# design.net
KiCad netlist of a schematic drawn in EasyEDA Pro
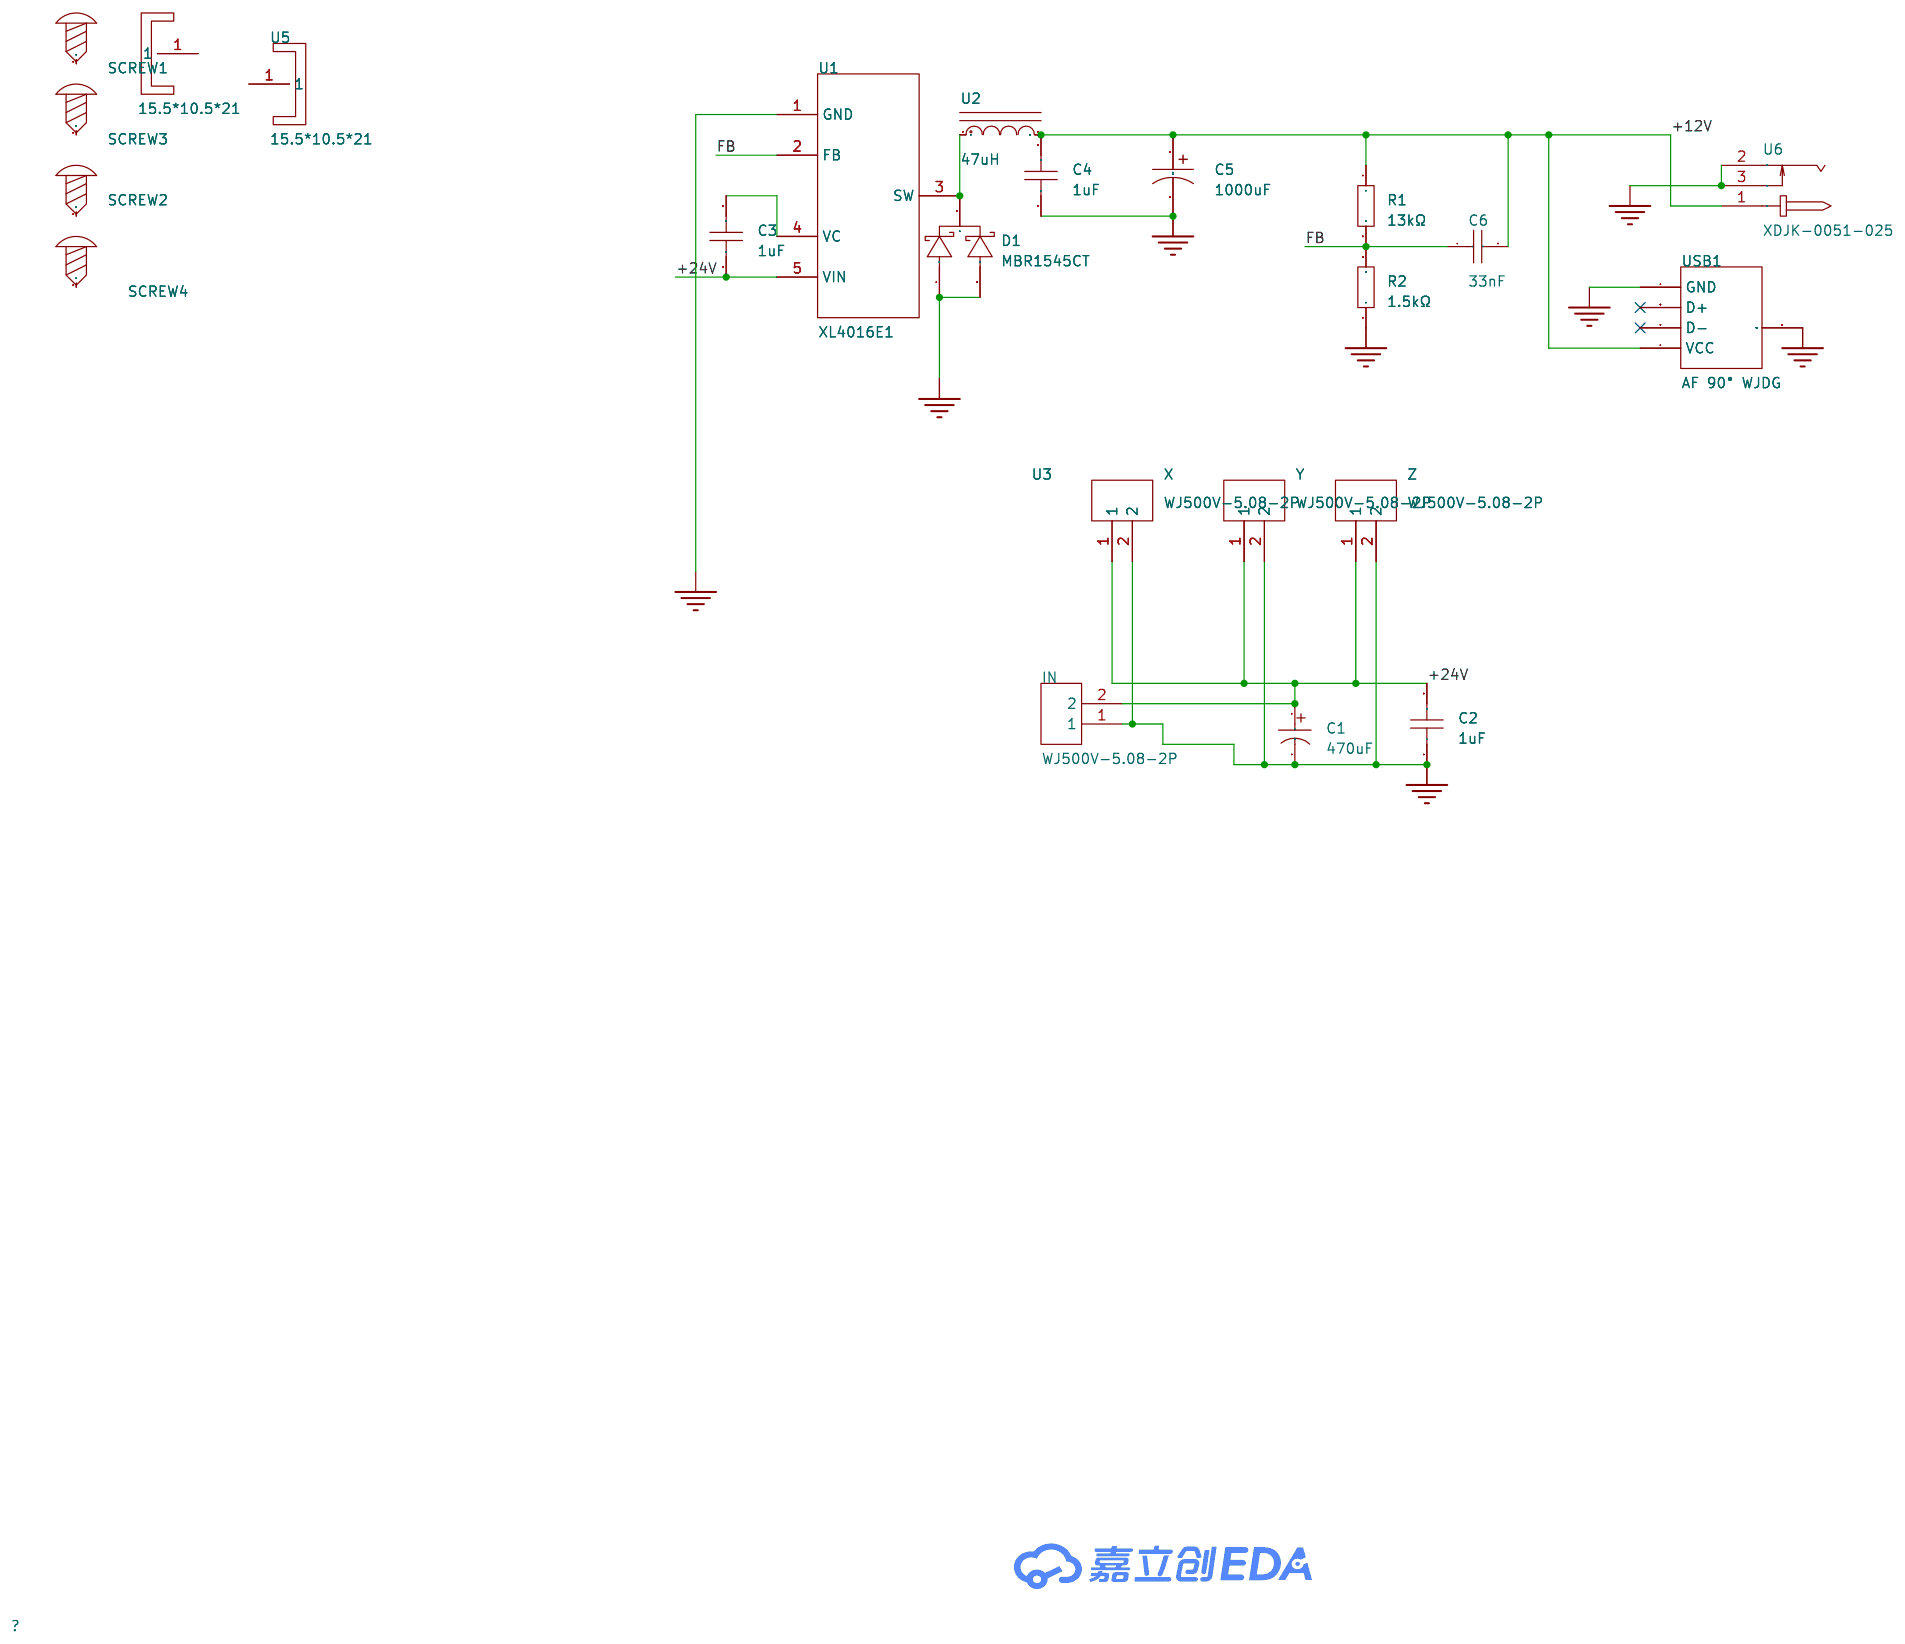
[diagram p0: schematic sheet]

(export (version "E")
  (design (tool "Eeschema 10.0.6"))
  (components
    (comp (ref "C1")
      (value "470uF")
      (footprint "easyedapro:CAP-TH_BD10.0-P5.00-D1.0-FD")
      (description "容值:470uF;精度:±20%;额定电压:50V;")
      (fields (field (name "Manufacturer Part") "ERS1HM471G20OT") (field (name "Manufacturer") "AISHI(艾华集团)"))
      (libsource (lib "easyedapro") (part "ERS1HM471G20OT"))
    )
    (comp (ref "C2")
      (value "1uF")
      (footprint "easyedapro:C0603")
      (description "容值:1uF;精度:±10%;额定电压:50V;材质(温度系数):X5R;")
      (fields
        (field (name "Manufacturer Part") "CL10A105KB8NNNC")
        (field (name "Manufacturer") "SAMSUNG(三星)")
      )
      (libsource (lib "easyedapro") (part "CL10A105KB8NNNC"))
    )
    (comp (ref "C3")
      (value "1uF")
      (footprint "easyedapro:C0603")
      (description "容值:1uF;精度:±10%;额定电压:50V;材质(温度系数):X5R;")
      (fields
        (field (name "Manufacturer Part") "CL10A105KB8NNNC")
        (field (name "Manufacturer") "SAMSUNG(三星)")
      )
      (libsource (lib "easyedapro") (part "CL10A105KB8NNNC"))
    )
    (comp (ref "C4")
      (value "1uF")
      (footprint "easyedapro:C0603")
      (description "容值:1uF;精度:±10%;额定电压:50V;材质(温度系数):X5R;")
      (fields
        (field (name "Manufacturer Part") "CL10A105KB8NNNC")
        (field (name "Manufacturer") "SAMSUNG(三星)")
      )
      (libsource (lib "easyedapro") (part "CL10A105KB8NNNC"))
    )
    (comp (ref "C5")
      (value "1000uF")
      (footprint "easyedapro:CAP-TH_BD10.0-P5.00-D1.0-FD")
      (description "容值:1000uF;精度:±20%;额定电压:25V;纹波电流:450mA@120Hz;等效串联电阻:-;")
      (fields
        (field (name "Manufacturer Part") "01EC4294SHC1000UF25V")
        (field (name "Manufacturer") "KNSCHA(科尼盛)")
      )
      (libsource (lib "easyedapro") (part "01EC4294SHC1000UF25V"))
    )
    (comp (ref "C6")
      (value "33nF")
      (footprint "easyedapro:C0603")
      (description "容值:33nF;精度:±10%;额定电压:50V;材质(温度系数):X7R;")
      (fields
        (field (name "Manufacturer Part") "CL10B333KB8NNNC")
        (field (name "Manufacturer") "SAMSUNG(三星)")
      )
      (libsource (lib "easyedapro") (part "CL10B333KB8NNNC"))
    )
    (comp (ref "D1")
      (value "MBR1545CT")
      (footprint "easyedapro:ITO-220AB-3_L10.0-W4.5-P2.54-R")
      (description "正向压降(Vf):650mV@7.5A;直流反向耐压(Vr):45V;整流电流:15A;")
      (fields (field (name "Manufacturer") "YANGJIE(扬杰)"))
      (libsource (lib "easyedapro") (part "MBR1545CT_C698791"))
    )
    (comp (ref "IN")
      (value "WJ500V-5.08-2P")
      (footprint "easyedapro:CONN-TH_2P-P5.00_WJ500V-5.08-2P")
      (fields (field (name "Manufacturer") "KANGNEX(康奈克斯电气)"))
      (libsource (lib "easyedapro") (part "WJ500V-5.08-2P-14-00A"))
    )
    (comp (ref "R1")
      (value "13kΩ")
      (footprint "easyedapro:R0603")
      (description "电阻类型:厚膜电阻;阻值:13kΩ;精度:±1%;功率:100mW;最大工作电压:75V;温度系数:±100ppm/°C;")
      (fields
        (field (name "Manufacturer Part") "0603WAF1302T5E")
        (field (name "Manufacturer") "UNI-ROYAL(厚声)")
      )
      (libsource (lib "easyedapro") (part "0603WAF1302T5E"))
    )
    (comp (ref "R2")
      (value "1.5kΩ")
      (footprint "easyedapro:R0603")
      (description "电阻类型:厚膜电阻;阻值:1.5kΩ;精度:±1%;功率:100mW;最大工作电压:75V;温度系数:±100ppm/°C;")
      (fields
        (field (name "Manufacturer Part") "0603WAF1501T5E")
        (field (name "Manufacturer") "UNI-ROYAL(厚声)")
      )
      (libsource (lib "easyedapro") (part "0603WAF1501T5E"))
    )
    (comp (ref "SCREW1")
      (value "~")
      (footprint "easyedapro:M3螺丝")
      (libsource (lib "easyedapro") (part "螺丝孔"))
    )
    (comp (ref "SCREW2")
      (value "~")
      (footprint "easyedapro:M3螺丝")
      (libsource (lib "easyedapro") (part "螺丝孔"))
    )
    (comp (ref "SCREW3")
      (value "~")
      (footprint "easyedapro:M3螺丝")
      (libsource (lib "easyedapro") (part "螺丝孔"))
    )
    (comp (ref "SCREW4")
      (value "~")
      (footprint "easyedapro:M3螺丝")
      (libsource (lib "easyedapro") (part "螺丝孔"))
    )
    (comp (ref "U1")
      (value "XL4016E1")
      (footprint "easyedapro:TO-220-5L_L10.2-W4.5-P1.71-L")
      (description "功能类型:降压型;输出类型:可调;工作电压:8V~36V;输出电压:1.25V~32V;输出电流:12A;")
      (fields (field (name "Manufacturer") "XLSEMI(芯龙)"))
      (libsource (lib "easyedapro") (part "XL4016E1"))
    )
    (comp (ref "U2")
      (value "47uH")
      (footprint "easyedapro:IND-TH_L23.2-W9.8_XR080125T101MV1L")
      (description "电感值:47uH;精度:±10%;额定电流:7.8A;类型:磁环电感;")
      (fields (field (name "Manufacturer Part") "XR080125T470MV1L") (field (name "Manufacturer") "XR(祥如)"))
      (libsource (lib "easyedapro") (part "XR080125T470MV1L"))
    )
    (comp (ref "U3")
      (value "15.5*10.5*21")
      (footprint "easyedapro:SINK-TH_L15.0-W10.5-H21.0")
      (description "产品尺寸:15.5*10.5*21MM;材 质:6063-T5;")
      (fields (field (name "Manufacturer") "XSD(鑫顺达)"))
      (libsource (lib "easyedapro") (part "15*10.5*21"))
    )
    (comp (ref "U5")
      (value "15.5*10.5*21")
      (footprint "easyedapro:SINK-TH_L15.0-W10.5-H21.0")
      (description "产品尺寸:15.5*10.5*21MM;材 质:6063-T5;")
      (fields (field (name "Manufacturer") "XSD(鑫顺达)"))
      (libsource (lib "easyedapro") (part "15*10.5*21"))
    )
    (comp (ref "U6")
      (value "XDJK-0051-025")
      (footprint "easyedapro:DC-IN-TH_XDJK-0051-025")
      (fields (field (name "Manufacturer") "LX(连欣科技)"))
      (libsource (lib "easyedapro") (part "XDJK-0051-025"))
    )
    (comp (ref "USB1")
      (value "AF 90° WJDG")
      (footprint "easyedapro:USB-A-TH_AF-WJDG")
      (description "连接器类型:Type-A;标准:USB 2.0;公母:母;安装方式:弯插;触点数量:4P;端口数量:1;额定电流 - 电源:1.5A;工作温度范围:-25°C~+85°C;")
      (fields (field (name "Manufacturer") "SHOU HAN(首韩)"))
      (libsource (lib "easyedapro") (part "AF 90° WJDG"))
    )
    (comp (ref "X")
      (value "WJ500V-5.08-2P")
      (footprint "easyedapro:CONN-TH_2P-P5.00_WJ500V-5.08-2P")
      (fields (field (name "Manufacturer") "KANGNEX(康奈克斯电气)"))
      (libsource (lib "easyedapro") (part "WJ500V-5.08-2P-14-00A"))
    )
    (comp (ref "Y")
      (value "WJ500V-5.08-2P")
      (footprint "easyedapro:CONN-TH_2P-P5.00_WJ500V-5.08-2P")
      (fields (field (name "Manufacturer") "KANGNEX(康奈克斯电气)"))
      (libsource (lib "easyedapro") (part "WJ500V-5.08-2P-14-00A"))
    )
    (comp (ref "Z")
      (value "WJ500V-5.08-2P")
      (footprint "easyedapro:CONN-TH_2P-P5.00_WJ500V-5.08-2P")
      (fields (field (name "Manufacturer") "KANGNEX(康奈克斯电气)"))
      (libsource (lib "easyedapro") (part "WJ500V-5.08-2P-14-00A"))
    )
  )
  (nets
    (net (code "1") (name "/+12V") (class "Default")
      (node (ref "C4") (pin "2") (pinfunction "2_2") (pintype "unspecified"))
      (node (ref "C5") (pin "1") (pinfunction "1_1") (pintype "unspecified"))
      (node (ref "C6") (pin "2") (pinfunction "2_2") (pintype "input"))
      (node (ref "R1") (pin "1") (pinfunction "1_1") (pintype "input"))
      (node (ref "U2") (pin "2") (pinfunction "2_2") (pintype "unspecified"))
      (node (ref "U6") (pin "1") (pinfunction "1_1") (pintype "unspecified"))
      (node (ref "USB1") (pin "1") (pinfunction "VCC_1") (pintype "input"))
    )
    (net (code "2") (name "/+24V") (class "Default")
      (node (ref "C1") (pin "1") (pinfunction "1_1") (pintype "input"))
      (node (ref "C2") (pin "2") (pinfunction "2_2") (pintype "unspecified"))
      (node (ref "C3") (pin "1") (pinfunction "1_1") (pintype "unspecified"))
      (node (ref "IN") (pin "2") (pinfunction "2_2") (pintype "unspecified"))
      (node (ref "U1") (pin "5") (pinfunction "VIN_5") (pintype "unspecified"))
      (node (ref "X") (pin "1") (pinfunction "1_1") (pintype "unspecified"))
      (node (ref "Y") (pin "1") (pinfunction "1_1") (pintype "unspecified"))
      (node (ref "Z") (pin "1") (pinfunction "1_1") (pintype "unspecified"))
    )
    (net (code "3") (name "/FB") (class "Default")
      (node (ref "C6") (pin "1") (pinfunction "1_1") (pintype "input"))
      (node (ref "R1") (pin "2") (pinfunction "2_2") (pintype "input"))
      (node (ref "R2") (pin "2") (pinfunction "2_2") (pintype "input"))
      (node (ref "U1") (pin "2") (pinfunction "FB_2") (pintype "unspecified"))
    )
    (net (code "4") (name "GND") (class "Default")
      (node (ref "C1") (pin "2") (pinfunction "2_2") (pintype "input"))
      (node (ref "C2") (pin "1") (pinfunction "1_1") (pintype "unspecified"))
      (node (ref "C4") (pin "1") (pinfunction "1_1") (pintype "unspecified"))
      (node (ref "C5") (pin "2") (pinfunction "2_2") (pintype "unspecified"))
      (node (ref "D1") (pin "1") (pinfunction "1_1") (pintype "unspecified"))
      (node (ref "D1") (pin "3") (pinfunction "3_3") (pintype "unspecified"))
      (node (ref "IN") (pin "1") (pinfunction "1_1") (pintype "unspecified"))
      (node (ref "R2") (pin "1") (pinfunction "1_1") (pintype "input"))
      (node (ref "U1") (pin "1") (pinfunction "GND_1") (pintype "unspecified"))
      (node (ref "U6") (pin "2") (pinfunction "2_2") (pintype "unspecified"))
      (node (ref "U6") (pin "3") (pinfunction "3_3") (pintype "unspecified"))
      (node (ref "USB1") (pin "4") (pinfunction "GND_4") (pintype "input"))
      (node (ref "USB1") (pin "5") (pinfunction "SHLD_5") (pintype "unspecified"))
      (node (ref "X") (pin "2") (pinfunction "2_2") (pintype "unspecified"))
      (node (ref "Y") (pin "2") (pinfunction "2_2") (pintype "unspecified"))
      (node (ref "Z") (pin "2") (pinfunction "2_2") (pintype "unspecified"))
    )
    (net (code "5") (name "Net-(U1-SW)") (class "Default")
      (node (ref "D1") (pin "2") (pinfunction "2_2") (pintype "unspecified"))
      (node (ref "U1") (pin "3") (pinfunction "SW_3") (pintype "unspecified"))
      (node (ref "U2") (pin "1") (pinfunction "1_1") (pintype "unspecified"))
    )
    (net (code "6") (name "Net-(U1-VC)") (class "Default")
      (node (ref "C3") (pin "2") (pinfunction "2_2") (pintype "unspecified"))
      (node (ref "U1") (pin "4") (pinfunction "VC_4") (pintype "unspecified"))
    )
    (net (code "7") (name "unconnected-(SCREW1-Pad1)") (class "Default")
      (node (ref "SCREW1") (pin "1") (pinfunction "1_1") (pintype "input"))
    )
    (net (code "8") (name "unconnected-(SCREW2-Pad1)") (class "Default")
      (node (ref "SCREW2") (pin "1") (pinfunction "1_1") (pintype "input"))
    )
    (net (code "9") (name "unconnected-(SCREW3-Pad1)") (class "Default")
      (node (ref "SCREW3") (pin "1") (pinfunction "1_1") (pintype "input"))
    )
    (net (code "10") (name "unconnected-(SCREW4-Pad1)") (class "Default")
      (node (ref "SCREW4") (pin "1") (pinfunction "1_1") (pintype "input"))
    )
    (net (code "11") (name "unconnected-(U3-Pad1)") (class "Default")
      (node (ref "U3") (pin "1") (pinfunction "1_1") (pintype "unspecified"))
    )
    (net (code "12") (name "unconnected-(U5-Pad1)") (class "Default")
      (node (ref "U5") (pin "1") (pinfunction "1_1") (pintype "unspecified"))
    )
    (net (code "13") (name "unconnected-(USB1-D+-Pad3)") (class "Default")
      (node (ref "USB1") (pin "3") (pinfunction "D+_3") (pintype "input+no_connect"))
    )
    (net (code "14") (name "unconnected-(USB1-D--Pad2)") (class "Default")
      (node (ref "USB1") (pin "2") (pinfunction "D-_2") (pintype "input+no_connect"))
    )
  )
)
